# Pi3_motor_hat_rev1.net
KiCad netlist of a schematic drawn in EAGLE
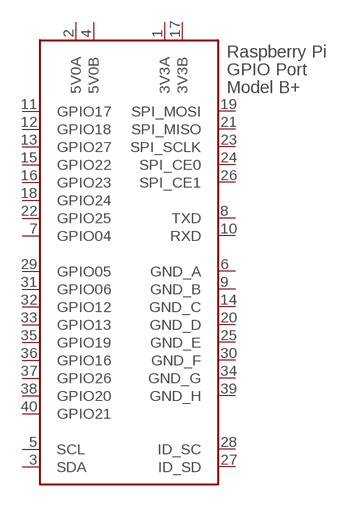
[diagram p0: schematic, sheet 1]
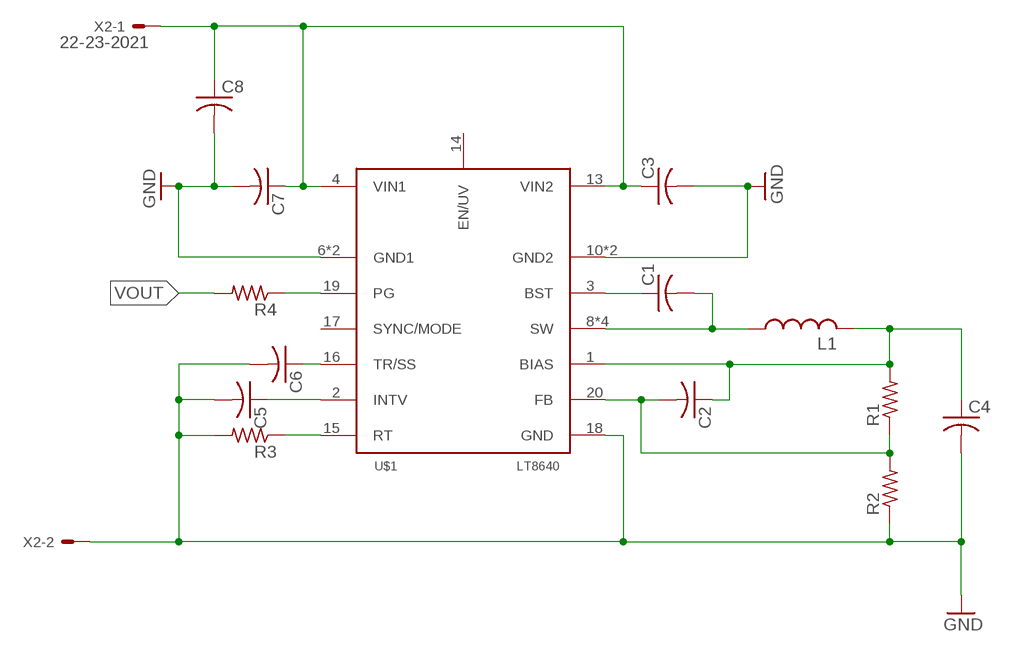
[diagram p1: schematic, sheet 2]

(export (version "E")
  (design (tool "Eeschema 10.0.6"))
  (components
    (comp (ref "X1")
      (value "RASPI_BOARD_B+#_HDC")
      (footprint "eagle-import:RASPI_BOARD_B+HAT_DF_CF")
      (libsource (lib "eagle-import") (part "RASPI_BOARD_B+#_HDC"))
    )
    (comp (ref "C1")
      (value "C-USC0402")
      (footprint "eagle-import:C0402")
      (libsource (lib "eagle-import") (part "C-USC0402"))
    )
    (comp (ref "C2")
      (value "C-USC0402")
      (footprint "eagle-import:C0402")
      (libsource (lib "eagle-import") (part "C-USC0402"))
    )
    (comp (ref "C3")
      (value "C-USC0402")
      (footprint "eagle-import:C0402")
      (libsource (lib "eagle-import") (part "C-USC0402"))
    )
    (comp (ref "C4")
      (value "C-USC1210")
      (footprint "eagle-import:C1210")
      (libsource (lib "eagle-import") (part "C-USC1210"))
    )
    (comp (ref "C5")
      (value "C-USC0402")
      (footprint "eagle-import:C0402")
      (libsource (lib "eagle-import") (part "C-USC0402"))
    )
    (comp (ref "C6")
      (value "C-USC0402")
      (footprint "eagle-import:C0402")
      (libsource (lib "eagle-import") (part "C-USC0402"))
    )
    (comp (ref "C7")
      (value "C-USC0402")
      (footprint "eagle-import:C0402")
      (libsource (lib "eagle-import") (part "C-USC0402"))
    )
    (comp (ref "C8")
      (value "C-USC0603")
      (footprint "eagle-import:C0603")
      (libsource (lib "eagle-import") (part "C-USC0603"))
    )
    (comp (ref "L1")
      (value "L-USIHLP2525EZER4R7M01")
      (footprint "eagle-import:IHLP2525EZER4R7M01-FOOT")
      (libsource (lib "eagle-import") (part "L-USIHLP2525EZER4R7M01"))
    )
    (comp (ref "R1")
      (value "R-US_R0402")
      (footprint "eagle-import:R0402")
      (libsource (lib "eagle-import") (part "R-US_R0402"))
    )
    (comp (ref "R2")
      (value "R-US_R0402")
      (footprint "eagle-import:R0402")
      (libsource (lib "eagle-import") (part "R-US_R0402"))
    )
    (comp (ref "R3")
      (value "R-US_R0402")
      (footprint "eagle-import:R0402")
      (libsource (lib "eagle-import") (part "R-US_R0402"))
    )
    (comp (ref "R4")
      (value "R-US_R0402")
      (footprint "eagle-import:R0402")
      (libsource (lib "eagle-import") (part "R-US_R0402"))
    )
    (comp (ref "U$1")
      (value "LT8640")
      (footprint "eagle-import:LT8640_FOOT")
      (libsource (lib "eagle-import") (part "LT8640"))
    )
    (comp (ref "X2")
      (value "22-23-2021")
      (footprint "eagle-import:22-23-2021")
      (fields (field (name "MF") "MOLEX"))
      (libsource (lib "eagle-import") (part "22-23-2021"))
    )
  )
  (nets
    (net (code "1") (name "3V3A") (class "Default")
      (node (ref "X1") (pin "1") (pinfunction "3V3A_1") (pintype "power_in"))
    )
    (net (code "2") (name "3V3B") (class "Default")
      (node (ref "X1") (pin "17") (pinfunction "3V3B_17") (pintype "power_in"))
    )
    (net (code "3") (name "5V0A") (class "Default")
      (node (ref "X1") (pin "2") (pinfunction "5V0A_2") (pintype "power_in"))
    )
    (net (code "4") (name "5V0B") (class "Default")
      (node (ref "X1") (pin "4") (pinfunction "5V0B_4") (pintype "power_in"))
    )
    (net (code "5") (name "GND") (class "Default")
      (node (ref "C3") (pin "2") (pinfunction "2_2") (pintype "passive"))
      (node (ref "C4") (pin "2") (pinfunction "2_2") (pintype "passive"))
      (node (ref "C5") (pin "2") (pinfunction "2_2") (pintype "passive"))
      (node (ref "C6") (pin "2") (pinfunction "2_2") (pintype "passive"))
      (node (ref "C7") (pin "2") (pinfunction "2_2") (pintype "passive"))
      (node (ref "C8") (pin "2") (pinfunction "2_2") (pintype "passive"))
      (node (ref "R2") (pin "1") (pinfunction "1_1") (pintype "passive"))
      (node (ref "R3") (pin "2") (pinfunction "2_2") (pintype "passive"))
      (node (ref "U$1") (pin "10") (pinfunction "GND2_10") (pintype "bidirectional"))
      (node (ref "U$1") (pin "11") (pinfunction "GND2_11") (pintype "bidirectional"))
      (node (ref "U$1") (pin "18") (pinfunction "GND_18") (pintype "bidirectional"))
      (node (ref "U$1") (pin "6") (pinfunction "GND1_6") (pintype "bidirectional"))
      (node (ref "U$1") (pin "7") (pinfunction "GND1_7") (pintype "bidirectional"))
      (node (ref "X2") (pin "2") (pinfunction "S_2") (pintype "passive"))
    )
    (net (code "6") (name "GND_A") (class "Default")
      (node (ref "X1") (pin "6") (pinfunction "GND_A_6") (pintype "power_in"))
    )
    (net (code "7") (name "GND_B") (class "Default")
      (node (ref "X1") (pin "9") (pinfunction "GND_B_9") (pintype "power_in"))
    )
    (net (code "8") (name "GND_C") (class "Default")
      (node (ref "X1") (pin "14") (pinfunction "GND_C_14") (pintype "power_in"))
    )
    (net (code "9") (name "GND_D") (class "Default")
      (node (ref "X1") (pin "20") (pinfunction "GND_D_20") (pintype "power_in"))
    )
    (net (code "10") (name "GND_E") (class "Default")
      (node (ref "X1") (pin "25") (pinfunction "GND_E_25") (pintype "power_in"))
    )
    (net (code "11") (name "GND_F") (class "Default")
      (node (ref "X1") (pin "30") (pinfunction "GND_F_30") (pintype "power_in"))
    )
    (net (code "12") (name "GND_G") (class "Default")
      (node (ref "X1") (pin "34") (pinfunction "GND_G_34") (pintype "power_in"))
    )
    (net (code "13") (name "GND_H") (class "Default")
      (node (ref "X1") (pin "39") (pinfunction "GND_H_39") (pintype "power_in"))
    )
    (net (code "14") (name "Net-(C1-Pad2)") (class "Default")
      (node (ref "C1") (pin "2") (pinfunction "2_2") (pintype "passive"))
      (node (ref "L1") (pin "1") (pinfunction "1_1") (pintype "passive"))
      (node (ref "U$1") (pin "21") (pinfunction "SW_21") (pintype "bidirectional"))
      (node (ref "U$1") (pin "22") (pinfunction "SW_22") (pintype "bidirectional"))
      (node (ref "U$1") (pin "8") (pinfunction "SW_8") (pintype "bidirectional"))
      (node (ref "U$1") (pin "9") (pinfunction "SW_9") (pintype "bidirectional"))
    )
    (net (code "15") (name "Net-(U$1-BST)") (class "Default")
      (node (ref "C1") (pin "1") (pinfunction "1_1") (pintype "passive"))
      (node (ref "U$1") (pin "3") (pinfunction "BST_3") (pintype "bidirectional"))
    )
    (net (code "16") (name "Net-(U$1-FB)") (class "Default")
      (node (ref "C2") (pin "2") (pinfunction "2_2") (pintype "passive"))
      (node (ref "R1") (pin "1") (pinfunction "1_1") (pintype "passive"))
      (node (ref "R2") (pin "2") (pinfunction "2_2") (pintype "passive"))
      (node (ref "U$1") (pin "20") (pinfunction "FB_20") (pintype "bidirectional"))
    )
    (net (code "17") (name "Net-(U$1-INTV)") (class "Default")
      (node (ref "C5") (pin "1") (pinfunction "1_1") (pintype "passive"))
      (node (ref "U$1") (pin "2") (pinfunction "INTV_2") (pintype "bidirectional"))
    )
    (net (code "18") (name "Net-(U$1-PG)") (class "Default")
      (node (ref "R4") (pin "1") (pinfunction "1_1") (pintype "passive"))
      (node (ref "U$1") (pin "19") (pinfunction "PG_19") (pintype "bidirectional"))
    )
    (net (code "19") (name "Net-(U$1-RT)") (class "Default")
      (node (ref "R3") (pin "1") (pinfunction "1_1") (pintype "passive"))
      (node (ref "U$1") (pin "15") (pinfunction "RT_15") (pintype "bidirectional"))
    )
    (net (code "20") (name "Net-(U$1-TR{slash}SS)") (class "Default")
      (node (ref "C6") (pin "1") (pinfunction "1_1") (pintype "passive"))
      (node (ref "U$1") (pin "16") (pinfunction "TR/SS_16") (pintype "bidirectional"))
    )
    (net (code "21") (name "Net-(U$1-VIN1)") (class "Default")
      (node (ref "C3") (pin "1") (pinfunction "1_1") (pintype "passive"))
      (node (ref "C7") (pin "1") (pinfunction "1_1") (pintype "passive"))
      (node (ref "C8") (pin "1") (pinfunction "1_1") (pintype "passive"))
      (node (ref "U$1") (pin "13") (pinfunction "VIN2_13") (pintype "bidirectional"))
      (node (ref "U$1") (pin "4") (pinfunction "VIN1_4") (pintype "bidirectional"))
      (node (ref "X2") (pin "1") (pinfunction "S_1") (pintype "passive"))
    )
    (net (code "22") (name "VOUT") (class "Default")
      (node (ref "C2") (pin "1") (pinfunction "1_1") (pintype "passive"))
      (node (ref "C4") (pin "1") (pinfunction "1_1") (pintype "passive"))
      (node (ref "L1") (pin "2") (pinfunction "2_2") (pintype "passive"))
      (node (ref "R1") (pin "2") (pinfunction "2_2") (pintype "passive"))
      (node (ref "R4") (pin "2") (pinfunction "2_2") (pintype "passive"))
      (node (ref "U$1") (pin "1") (pinfunction "BIAS_1") (pintype "bidirectional"))
    )
    (net (code "23") (name "unconnected-(U$1-EN{slash}UV-Pad14)") (class "Default")
      (node (ref "U$1") (pin "14") (pinfunction "EN/UV_14") (pintype "bidirectional"))
    )
    (net (code "24") (name "unconnected-(U$1-SYNC{slash}MODE-Pad17)") (class "Default")
      (node (ref "U$1") (pin "17") (pinfunction "SYNC/MODE_17") (pintype "bidirectional"))
    )
    (net (code "25") (name "unconnected-(X1-GPIO04-Pad7)") (class "Default")
      (node (ref "X1") (pin "7") (pinfunction "GPIO04_7") (pintype "bidirectional"))
    )
    (net (code "26") (name "unconnected-(X1-GPIO05-Pad29)") (class "Default")
      (node (ref "X1") (pin "29") (pinfunction "GPIO05_29") (pintype "no_connect"))
    )
    (net (code "27") (name "unconnected-(X1-GPIO06-Pad31)") (class "Default")
      (node (ref "X1") (pin "31") (pinfunction "GPIO06_31") (pintype "no_connect"))
    )
    (net (code "28") (name "unconnected-(X1-GPIO12-Pad32)") (class "Default")
      (node (ref "X1") (pin "32") (pinfunction "GPIO12_32") (pintype "no_connect"))
    )
    (net (code "29") (name "unconnected-(X1-GPIO13-Pad33)") (class "Default")
      (node (ref "X1") (pin "33") (pinfunction "GPIO13_33") (pintype "no_connect"))
    )
    (net (code "30") (name "unconnected-(X1-GPIO16-Pad36)") (class "Default")
      (node (ref "X1") (pin "36") (pinfunction "GPIO16_36") (pintype "no_connect"))
    )
    (net (code "31") (name "unconnected-(X1-GPIO17-Pad11)") (class "Default")
      (node (ref "X1") (pin "11") (pinfunction "GPIO17_11") (pintype "bidirectional"))
    )
    (net (code "32") (name "unconnected-(X1-GPIO18-Pad12)") (class "Default")
      (node (ref "X1") (pin "12") (pinfunction "GPIO18_12") (pintype "bidirectional"))
    )
    (net (code "33") (name "unconnected-(X1-GPIO19-Pad35)") (class "Default")
      (node (ref "X1") (pin "35") (pinfunction "GPIO19_35") (pintype "no_connect"))
    )
    (net (code "34") (name "unconnected-(X1-GPIO20-Pad38)") (class "Default")
      (node (ref "X1") (pin "38") (pinfunction "GPIO20_38") (pintype "no_connect"))
    )
    (net (code "35") (name "unconnected-(X1-GPIO21-Pad40)") (class "Default")
      (node (ref "X1") (pin "40") (pinfunction "GPIO21_40") (pintype "no_connect"))
    )
    (net (code "36") (name "unconnected-(X1-GPIO22-Pad15)") (class "Default")
      (node (ref "X1") (pin "15") (pinfunction "GPIO22_15") (pintype "bidirectional"))
    )
    (net (code "37") (name "unconnected-(X1-GPIO23-Pad16)") (class "Default")
      (node (ref "X1") (pin "16") (pinfunction "GPIO23_16") (pintype "bidirectional"))
    )
    (net (code "38") (name "unconnected-(X1-GPIO24-Pad18)") (class "Default")
      (node (ref "X1") (pin "18") (pinfunction "GPIO24_18") (pintype "bidirectional"))
    )
    (net (code "39") (name "unconnected-(X1-GPIO25-Pad22)") (class "Default")
      (node (ref "X1") (pin "22") (pinfunction "GPIO25_22") (pintype "bidirectional"))
    )
    (net (code "40") (name "unconnected-(X1-GPIO26-Pad37)") (class "Default")
      (node (ref "X1") (pin "37") (pinfunction "GPIO26_37") (pintype "no_connect"))
    )
    (net (code "41") (name "unconnected-(X1-GPIO27-Pad13)") (class "Default")
      (node (ref "X1") (pin "13") (pinfunction "GPIO27_13") (pintype "bidirectional"))
    )
    (net (code "42") (name "unconnected-(X1-ID_SC-Pad28)") (class "Default")
      (node (ref "X1") (pin "28") (pinfunction "ID_SC_28") (pintype "no_connect"))
    )
    (net (code "43") (name "unconnected-(X1-ID_SD-Pad27)") (class "Default")
      (node (ref "X1") (pin "27") (pinfunction "ID_SD_27") (pintype "no_connect"))
    )
    (net (code "44") (name "unconnected-(X1-RXD-Pad10)") (class "Default")
      (node (ref "X1") (pin "10") (pinfunction "RXD_10") (pintype "bidirectional"))
    )
    (net (code "45") (name "unconnected-(X1-SCL-Pad5)") (class "Default")
      (node (ref "X1") (pin "5") (pinfunction "SCL_5") (pintype "bidirectional"))
    )
    (net (code "46") (name "unconnected-(X1-SDA-Pad3)") (class "Default")
      (node (ref "X1") (pin "3") (pinfunction "SDA_3") (pintype "bidirectional"))
    )
    (net (code "47") (name "unconnected-(X1-SPI_CE0-Pad24)") (class "Default")
      (node (ref "X1") (pin "24") (pinfunction "SPI_CE0_24") (pintype "bidirectional"))
    )
    (net (code "48") (name "unconnected-(X1-SPI_CE1-Pad26)") (class "Default")
      (node (ref "X1") (pin "26") (pinfunction "SPI_CE1_26") (pintype "bidirectional"))
    )
    (net (code "49") (name "unconnected-(X1-SPI_MISO-Pad21)") (class "Default")
      (node (ref "X1") (pin "21") (pinfunction "SPI_MISO_21") (pintype "bidirectional"))
    )
    (net (code "50") (name "unconnected-(X1-SPI_MOSI-Pad19)") (class "Default")
      (node (ref "X1") (pin "19") (pinfunction "SPI_MOSI_19") (pintype "bidirectional"))
    )
    (net (code "51") (name "unconnected-(X1-SPI_SCLK-Pad23)") (class "Default")
      (node (ref "X1") (pin "23") (pinfunction "SPI_SCLK_23") (pintype "bidirectional"))
    )
    (net (code "52") (name "unconnected-(X1-TXD-Pad8)") (class "Default")
      (node (ref "X1") (pin "8") (pinfunction "TXD_8") (pintype "bidirectional"))
    )
  )
)
